# BEATS_3_6.net
KiCad netlist of a schematic drawn in EAGLE
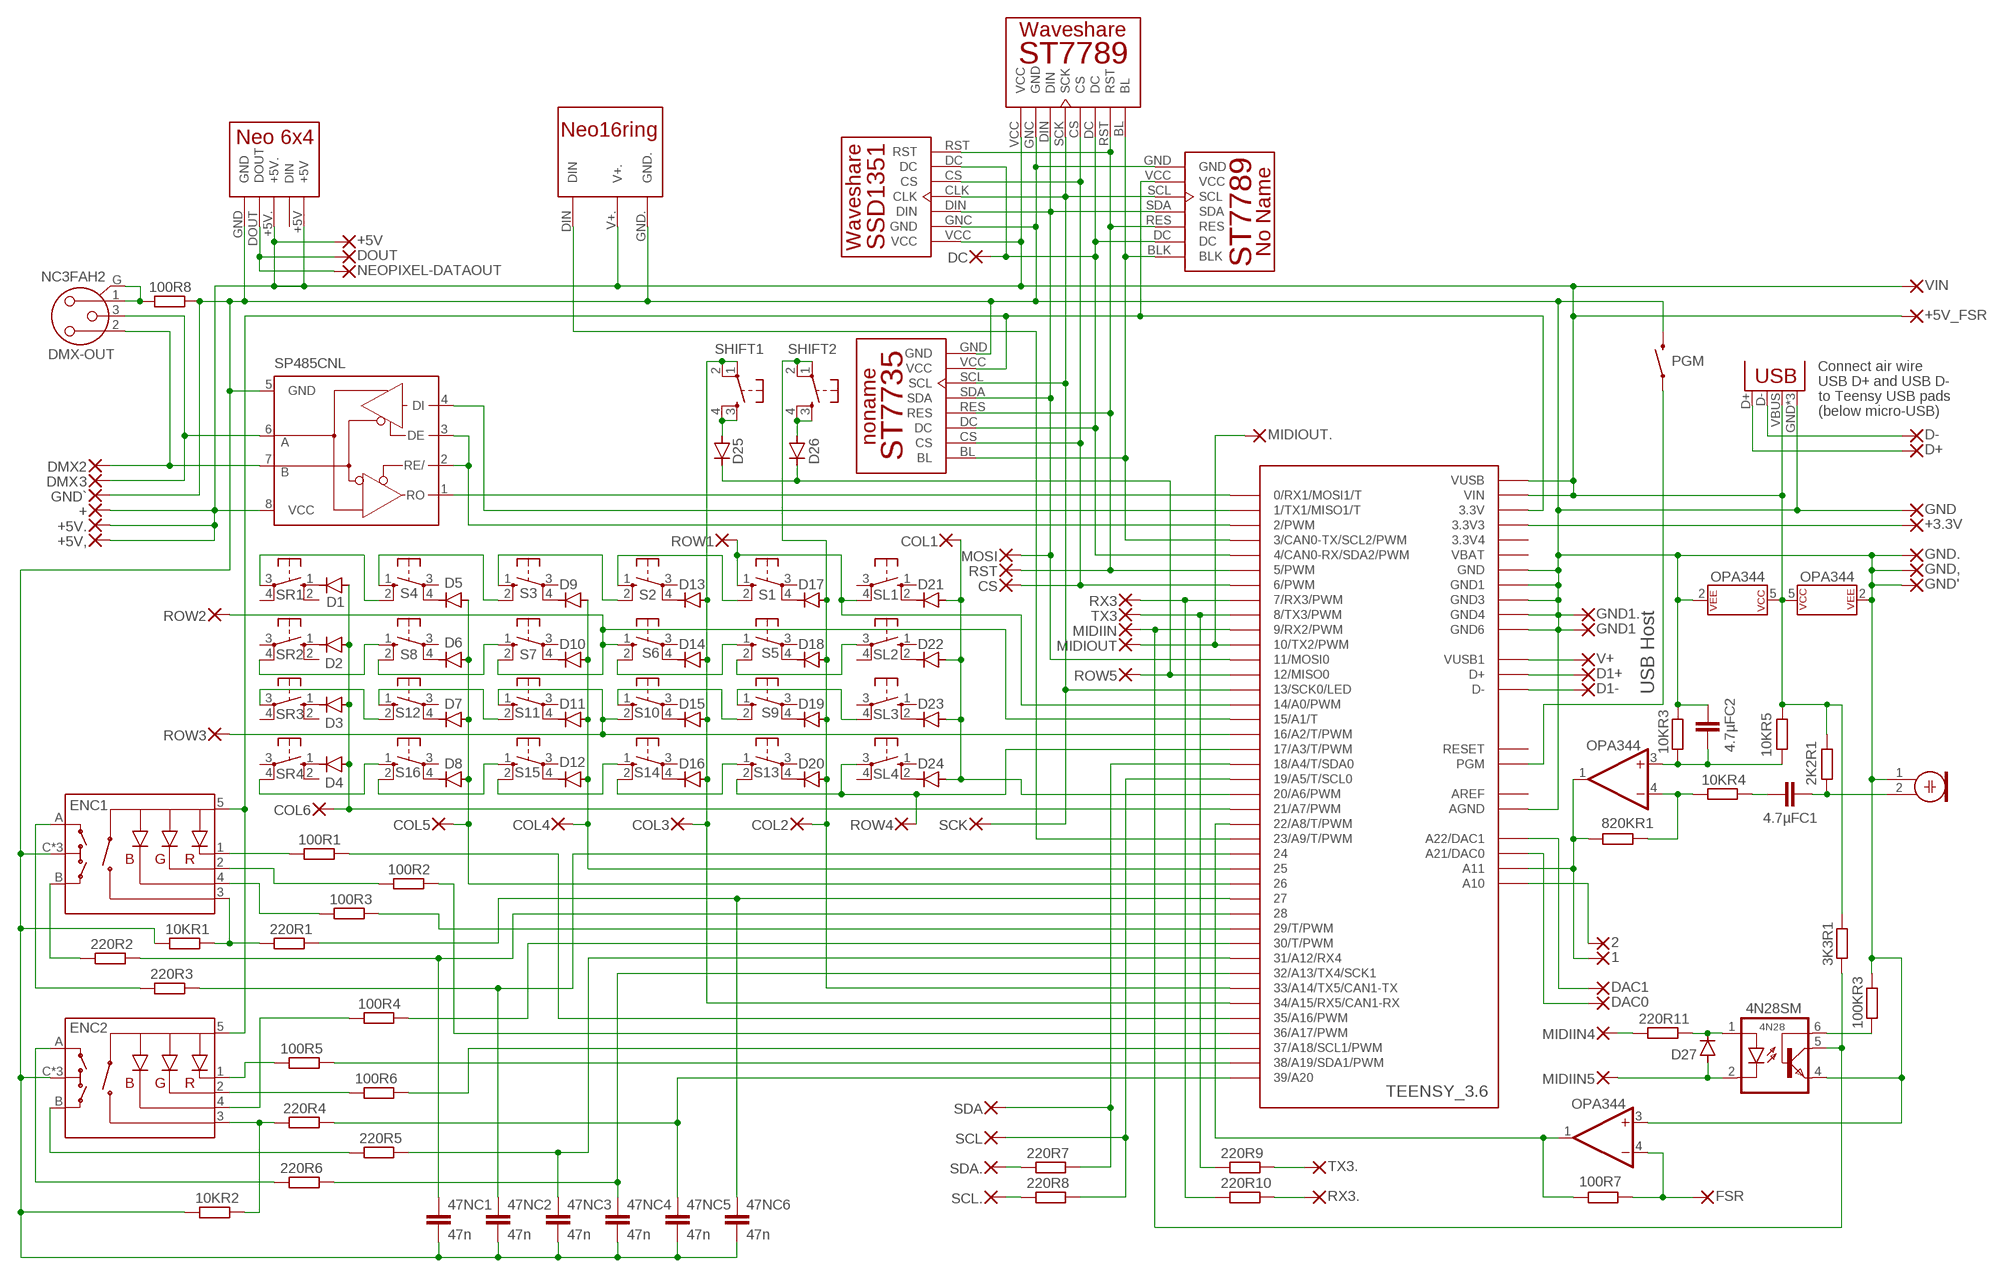
[diagram p0: schematic, sheet 1]

(export (version "E")
  (design (tool "Eeschema 10.0.6"))
  (components
    (comp (ref "+")
      (value "1,6/0,8")
      (footprint "eagle-import:1,6_0,8")
      (libsource (lib "eagle-import") (part "1,6/0,8"))
    )
    (comp (ref "+3.3V")
      (value "+3.3v")
      (footprint "eagle-import:1,6_0,8")
      (libsource (lib "eagle-import") (part "1,6/0,8"))
    )
    (comp (ref "+5V")
      (value "1,6/0,8")
      (footprint "eagle-import:1,6_0,8")
      (libsource (lib "eagle-import") (part "1,6/0,8"))
    )
    (comp (ref "+5V,")
      (value "1,6/0,8")
      (footprint "eagle-import:1,6_0,8")
      (libsource (lib "eagle-import") (part "1,6/0,8"))
    )
    (comp (ref "+5V.")
      (value "1,6/0,8")
      (footprint "eagle-import:1,6_0,8")
      (libsource (lib "eagle-import") (part "1,6/0,8"))
    )
    (comp (ref "+5V_FSR")
      (value "1,6/0,8")
      (footprint "eagle-import:1,6_0,8")
      (libsource (lib "eagle-import") (part "1,6/0,8"))
    )
    (comp (ref "1")
      (value "1,6/0,8")
      (footprint "eagle-import:1,6_0,8")
      (libsource (lib "eagle-import") (part "1,6/0,8"))
    )
    (comp (ref "2")
      (value "1,6/0,8")
      (footprint "eagle-import:1,6_0,8")
      (libsource (lib "eagle-import") (part "1,6/0,8"))
    )
    (comp (ref "2K2R1")
      (value "2K2")
      (footprint "eagle-import:R0603")
      (fields (field (name "SPICEPREFIX") "2K2"))
      (libsource (lib "eagle-import") (part "R-EU_R0603"))
    )
    (comp (ref "3")
      (value "1,6/0,8")
      (footprint "eagle-import:1,6_0,8")
      (libsource (lib "eagle-import") (part "1,6/0,8"))
    )
    (comp (ref "3K3R1")
      (value "3k3")
      (footprint "eagle-import:R0603")
      (fields (field (name "SPICEPREFIX") "3.3K"))
      (libsource (lib "eagle-import") (part "R-EU_R0603"))
    )
    (comp (ref "4.7µFC1")
      (value "4.7µF")
      (footprint "eagle-import:C1210")
      (libsource (lib "eagle-import") (part "rcl_334_C-EUC1210"))
    )
    (comp (ref "4.7µFC2")
      (value "4.7µF")
      (footprint "eagle-import:C1210")
      (libsource (lib "eagle-import") (part "rcl_334_C-EUC1210"))
    )
    (comp (ref "4N28")
      (value "4N28SM")
      (footprint "eagle-import:DIL6-SMD")
      (fields (field (name "MF") "FAIRCHILD SEMICONDUCTOR") (field (name "MPN") "4N28S-M"))
      (libsource (lib "eagle-import") (part "4N?MS28"))
    )
    (comp (ref "10KR1")
      (value "10k")
      (footprint "eagle-import:R0603")
      (fields (field (name "SPICEPREFIX") "2K2"))
      (libsource (lib "eagle-import") (part "R-EU_R0603"))
    )
    (comp (ref "10KR2")
      (value "10k")
      (footprint "eagle-import:R0603")
      (fields (field (name "SPICEPREFIX") "2K2"))
      (libsource (lib "eagle-import") (part "R-EU_R0603"))
    )
    (comp (ref "10KR3")
      (value "10K")
      (footprint "eagle-import:R0603")
      (fields (field (name "SPICEPREFIX") "10K"))
      (libsource (lib "eagle-import") (part "R-EU_R0603"))
    )
    (comp (ref "10KR4")
      (value "10K")
      (footprint "eagle-import:R0603")
      (fields (field (name "SPICEPREFIX") "10K"))
      (libsource (lib "eagle-import") (part "R-EU_R0603"))
    )
    (comp (ref "10KR5")
      (value "10K")
      (footprint "eagle-import:R0603")
      (fields (field (name "SPICEPREFIX") "10K"))
      (libsource (lib "eagle-import") (part "R-EU_R0603"))
    )
    (comp (ref "47NC1")
      (value "47n")
      (footprint "eagle-import:C0603")
      (libsource (lib "eagle-import") (part "C-EUC0603"))
    )
    (comp (ref "47NC2")
      (value "47n")
      (footprint "eagle-import:C0603")
      (libsource (lib "eagle-import") (part "C-EUC0603"))
    )
    (comp (ref "47NC3")
      (value "47n")
      (footprint "eagle-import:C0603")
      (libsource (lib "eagle-import") (part "C-EUC0603"))
    )
    (comp (ref "47NC4")
      (value "47n")
      (footprint "eagle-import:C0603")
      (libsource (lib "eagle-import") (part "C-EUC0603"))
    )
    (comp (ref "47NC5")
      (value "47n")
      (footprint "eagle-import:C0603")
      (libsource (lib "eagle-import") (part "C-EUC0603"))
    )
    (comp (ref "47NC6")
      (value "47n")
      (footprint "eagle-import:C0603")
      (libsource (lib "eagle-import") (part "C-EUC0603"))
    )
    (comp (ref "100KR3")
      (value "100k")
      (footprint "eagle-import:R0603")
      (fields (field (name "SPICEPREFIX") "100K"))
      (libsource (lib "eagle-import") (part "R-EU_R0603"))
    )
    (comp (ref "100R1")
      (value "220R")
      (footprint "eagle-import:R0603")
      (fields (field (name "SPICEPREFIX") "220R"))
      (libsource (lib "eagle-import") (part "R-EU_R0603"))
    )
    (comp (ref "100R2")
      (value "220R")
      (footprint "eagle-import:R0603")
      (fields (field (name "SPICEPREFIX") "220R"))
      (libsource (lib "eagle-import") (part "R-EU_R0603"))
    )
    (comp (ref "100R3")
      (value "220R")
      (footprint "eagle-import:R0603")
      (fields (field (name "SPICEPREFIX") "220R"))
      (libsource (lib "eagle-import") (part "R-EU_R0603"))
    )
    (comp (ref "100R4")
      (value "220R")
      (footprint "eagle-import:R0603")
      (fields (field (name "SPICEPREFIX") "220R"))
      (libsource (lib "eagle-import") (part "R-EU_R0603"))
    )
    (comp (ref "100R5")
      (value "220R")
      (footprint "eagle-import:R0603")
      (fields (field (name "SPICEPREFIX") "220R"))
      (libsource (lib "eagle-import") (part "R-EU_R0603"))
    )
    (comp (ref "100R6")
      (value "220R")
      (footprint "eagle-import:R0603")
      (fields (field (name "SPICEPREFIX") "220R"))
      (libsource (lib "eagle-import") (part "R-EU_R0603"))
    )
    (comp (ref "100R7")
      (value "100R")
      (footprint "eagle-import:R0603")
      (fields (field (name "SPICEPREFIX") "2K2"))
      (libsource (lib "eagle-import") (part "R-EU_R0603"))
    )
    (comp (ref "100R8")
      (value "220R")
      (footprint "eagle-import:R0603")
      (fields (field (name "SPICEPREFIX") "220R"))
      (libsource (lib "eagle-import") (part "R-EU_R0603"))
    )
    (comp (ref "220R1")
      (value "220R")
      (footprint "eagle-import:R0603")
      (fields (field (name "SPICEPREFIX") "220R"))
      (libsource (lib "eagle-import") (part "R-EU_R0603"))
    )
    (comp (ref "220R2")
      (value "220R")
      (footprint "eagle-import:R0603")
      (fields (field (name "SPICEPREFIX") "220R"))
      (libsource (lib "eagle-import") (part "R-EU_R0603"))
    )
    (comp (ref "220R3")
      (value "220R")
      (footprint "eagle-import:R0603")
      (fields (field (name "SPICEPREFIX") "220R"))
      (libsource (lib "eagle-import") (part "R-EU_R0603"))
    )
    (comp (ref "220R4")
      (value "220R")
      (footprint "eagle-import:R0603")
      (fields (field (name "SPICEPREFIX") "220R"))
      (libsource (lib "eagle-import") (part "R-EU_R0603"))
    )
    (comp (ref "220R5")
      (value "220R")
      (footprint "eagle-import:R0603")
      (fields (field (name "SPICEPREFIX") "220R"))
      (libsource (lib "eagle-import") (part "R-EU_R0603"))
    )
    (comp (ref "220R6")
      (value "220R")
      (footprint "eagle-import:R0603")
      (fields (field (name "SPICEPREFIX") "220R"))
      (libsource (lib "eagle-import") (part "R-EU_R0603"))
    )
    (comp (ref "220R7")
      (value "220R")
      (footprint "eagle-import:R0603")
      (fields (field (name "SPICEPREFIX") "220R"))
      (libsource (lib "eagle-import") (part "R-EU_R0603"))
    )
    (comp (ref "220R8")
      (value "220R")
      (footprint "eagle-import:R0603")
      (fields (field (name "SPICEPREFIX") "220R"))
      (libsource (lib "eagle-import") (part "R-EU_R0603"))
    )
    (comp (ref "220R9")
      (value "220R")
      (footprint "eagle-import:R0603")
      (fields (field (name "SPICEPREFIX") "220R"))
      (libsource (lib "eagle-import") (part "R-EU_R0603"))
    )
    (comp (ref "220R10")
      (value "220R")
      (footprint "eagle-import:R0603")
      (fields (field (name "SPICEPREFIX") "220R"))
      (libsource (lib "eagle-import") (part "R-EU_R0603"))
    )
    (comp (ref "220R11")
      (value "220R")
      (footprint "eagle-import:R0603")
      (fields (field (name "SPICEPREFIX") "220R"))
      (libsource (lib "eagle-import") (part "R-EU_R0603"))
    )
    (comp (ref "820KR1")
      (value "820K")
      (footprint "eagle-import:R0603")
      (fields (field (name "SPICEPREFIX") "820K"))
      (libsource (lib "eagle-import") (part "R-EU_R0603"))
    )
    (comp (ref "COL1")
      (value "1,6/0,8")
      (footprint "eagle-import:1,6_0,8")
      (libsource (lib "eagle-import") (part "1,6/0,8"))
    )
    (comp (ref "COL2")
      (value "1,6/0,8")
      (footprint "eagle-import:1,6_0,8")
      (libsource (lib "eagle-import") (part "1,6/0,8"))
    )
    (comp (ref "COL3")
      (value "1,6/0,8")
      (footprint "eagle-import:1,6_0,8")
      (libsource (lib "eagle-import") (part "1,6/0,8"))
    )
    (comp (ref "COL4")
      (value "1,6/0,8")
      (footprint "eagle-import:1,6_0,8")
      (libsource (lib "eagle-import") (part "1,6/0,8"))
    )
    (comp (ref "COL5")
      (value "1,6/0,8")
      (footprint "eagle-import:1,6_0,8")
      (libsource (lib "eagle-import") (part "1,6/0,8"))
    )
    (comp (ref "COL6")
      (value "1,6/0,8")
      (footprint "eagle-import:1,6_0,8")
      (libsource (lib "eagle-import") (part "1,6/0,8"))
    )
    (comp (ref "CS")
      (value "1,6/0,8")
      (footprint "eagle-import:1,6_0,8")
      (libsource (lib "eagle-import") (part "1,6/0,8"))
    )
    (comp (ref "D+")
      (value "1,6/0,8")
      (footprint "eagle-import:1,6_0,8")
      (libsource (lib "eagle-import") (part "1,6/0,8"))
    )
    (comp (ref "D-")
      (value "1,6/0,8")
      (footprint "eagle-import:1,6_0,8")
      (libsource (lib "eagle-import") (part "1,6/0,8"))
    )
    (comp (ref "D1")
      (value "1N4148DO34-5")
      (footprint "eagle-import:DO34-5")
      (libsource (lib "eagle-import") (part "1N4148DO34-5"))
    )
    (comp (ref "D1+")
      (value "1,6/0,8")
      (footprint "eagle-import:1,6_0,8")
      (libsource (lib "eagle-import") (part "1,6/0,8"))
    )
    (comp (ref "D1-")
      (value "1,6/0,8")
      (footprint "eagle-import:1,6_0,8")
      (libsource (lib "eagle-import") (part "1,6/0,8"))
    )
    (comp (ref "D2")
      (value "1N4148DO34-5")
      (footprint "eagle-import:DO34-5")
      (libsource (lib "eagle-import") (part "1N4148DO34-5"))
    )
    (comp (ref "D3")
      (value "1N4148DO34-5")
      (footprint "eagle-import:DO34-5")
      (libsource (lib "eagle-import") (part "1N4148DO34-5"))
    )
    (comp (ref "D4")
      (value "1N4148DO34-5")
      (footprint "eagle-import:DO34-5")
      (libsource (lib "eagle-import") (part "1N4148DO34-5"))
    )
    (comp (ref "D5")
      (value "1N4148DO34-5")
      (footprint "eagle-import:DO34-5")
      (libsource (lib "eagle-import") (part "1N4148DO34-5"))
    )
    (comp (ref "D6")
      (value "1N4148DO34-5")
      (footprint "eagle-import:DO34-5")
      (libsource (lib "eagle-import") (part "1N4148DO34-5"))
    )
    (comp (ref "D7")
      (value "1N4148DO34-5")
      (footprint "eagle-import:DO34-5")
      (libsource (lib "eagle-import") (part "1N4148DO34-5"))
    )
    (comp (ref "D8")
      (value "1N4148DO34-5")
      (footprint "eagle-import:DO34-5")
      (libsource (lib "eagle-import") (part "1N4148DO34-5"))
    )
    (comp (ref "D9")
      (value "1N4148DO34-5")
      (footprint "eagle-import:DO34-5")
      (libsource (lib "eagle-import") (part "1N4148DO34-5"))
    )
    (comp (ref "D10")
      (value "1N4148DO34-5")
      (footprint "eagle-import:DO34-5")
      (libsource (lib "eagle-import") (part "1N4148DO34-5"))
    )
    (comp (ref "D11")
      (value "1N4148DO34-5")
      (footprint "eagle-import:DO34-5")
      (libsource (lib "eagle-import") (part "1N4148DO34-5"))
    )
    (comp (ref "D12")
      (value "1N4148DO34-5")
      (footprint "eagle-import:DO34-5")
      (libsource (lib "eagle-import") (part "1N4148DO34-5"))
    )
    (comp (ref "D13")
      (value "1N4148DO34-5")
      (footprint "eagle-import:DO34-5")
      (libsource (lib "eagle-import") (part "1N4148DO34-5"))
    )
    (comp (ref "D14")
      (value "1N4148DO34-5")
      (footprint "eagle-import:DO34-5")
      (libsource (lib "eagle-import") (part "1N4148DO34-5"))
    )
    (comp (ref "D15")
      (value "1N4148DO34-5")
      (footprint "eagle-import:DO34-5")
      (libsource (lib "eagle-import") (part "1N4148DO34-5"))
    )
    (comp (ref "D16")
      (value "1N4148DO34-5")
      (footprint "eagle-import:DO34-5")
      (libsource (lib "eagle-import") (part "1N4148DO34-5"))
    )
    (comp (ref "D17")
      (value "1N4148DO34-5")
      (footprint "eagle-import:DO34-5")
      (libsource (lib "eagle-import") (part "1N4148DO34-5"))
    )
    (comp (ref "D18")
      (value "1N4148DO34-5")
      (footprint "eagle-import:DO34-5")
      (libsource (lib "eagle-import") (part "1N4148DO34-5"))
    )
    (comp (ref "D19")
      (value "1N4148DO34-5")
      (footprint "eagle-import:DO34-5")
      (libsource (lib "eagle-import") (part "1N4148DO34-5"))
    )
    (comp (ref "D20")
      (value "1N4148DO34-5")
      (footprint "eagle-import:DO34-5")
      (libsource (lib "eagle-import") (part "1N4148DO34-5"))
    )
    (comp (ref "D21")
      (value "1N4148DO34-5")
      (footprint "eagle-import:DO34-5")
      (libsource (lib "eagle-import") (part "1N4148DO34-5"))
    )
    (comp (ref "D22")
      (value "1N4148DO34-5")
      (footprint "eagle-import:DO34-5")
      (libsource (lib "eagle-import") (part "1N4148DO34-5"))
    )
    (comp (ref "D23")
      (value "1N4148DO34-5")
      (footprint "eagle-import:DO34-5")
      (libsource (lib "eagle-import") (part "1N4148DO34-5"))
    )
    (comp (ref "D24")
      (value "1N4148DO34-5")
      (footprint "eagle-import:DO34-5")
      (libsource (lib "eagle-import") (part "1N4148DO34-5"))
    )
    (comp (ref "D25")
      (value "1N4148DO34-5")
      (footprint "eagle-import:DO34-5")
      (libsource (lib "eagle-import") (part "1N4148DO34-5"))
    )
    (comp (ref "D26")
      (value "1N4148DO34-5")
      (footprint "eagle-import:DO34-5")
      (libsource (lib "eagle-import") (part "1N4148DO34-5"))
    )
    (comp (ref "D27")
      (value "1N4148DO34-5")
      (footprint "eagle-import:DO34-5")
      (libsource (lib "eagle-import") (part "1N4148DO34-5"))
    )
    (comp (ref "DAC0")
      (value "1,6/0,8")
      (footprint "eagle-import:1,6_0,8")
      (libsource (lib "eagle-import") (part "1,6/0,8"))
    )
    (comp (ref "DAC1")
      (value "1,6/0,8")
      (footprint "eagle-import:1,6_0,8")
      (libsource (lib "eagle-import") (part "1,6/0,8"))
    )
    (comp (ref "DC")
      (value "1,6/0,8")
      (footprint "eagle-import:1,6_0,8")
      (libsource (lib "eagle-import") (part "1,6/0,8"))
    )
    (comp (ref "DMX-OUT")
      (value "NC3FAH2")
      (footprint "eagle-import:NC3FAH2")
      (libsource (lib "eagle-import") (part "NC3FAH2"))
    )
    (comp (ref "DMX2")
      (value "1,6/0,8")
      (footprint "eagle-import:1,6_0,8")
      (libsource (lib "eagle-import") (part "1,6/0,8"))
    )
    (comp (ref "DOUT")
      (value "1,6/0,8")
      (footprint "eagle-import:1,6_0,8")
      (libsource (lib "eagle-import") (part "1,6/0,8"))
    )
    (comp (ref "ENC1")
      (value "ENCODER-RGB-SWITCHENCODER_LED_3_LONG")
      (footprint "eagle-import:ENCODER_LED_3_LONG")
      (libsource (lib "eagle-import") (part "ENCODER-RGB-SWITCHENCODER_LED_3_LONG"))
    )
    (comp (ref "ENC2")
      (value "ENCODER-RGB-SWITCHENCODER_LED_3_LONG")
      (footprint "eagle-import:ENCODER_LED_3_LONG")
      (libsource (lib "eagle-import") (part "ENCODER-RGB-SWITCHENCODER_LED_3_LONG"))
    )
    (comp (ref "FSR")
      (value "1,6/0,8")
      (footprint "eagle-import:1,6_0,8")
      (libsource (lib "eagle-import") (part "1,6/0,8"))
    )
    (comp (ref "GND")
      (value "1,6/0,8")
      (footprint "eagle-import:1,6_0,8")
      (libsource (lib "eagle-import") (part "1,6/0,8"))
    )
    (comp (ref "GND'")
      (value "1,6/0,8")
      (footprint "eagle-import:1,6_0,8")
      (libsource (lib "eagle-import") (part "1,6/0,8"))
    )
    (comp (ref "GND,")
      (value "1,6/0,8")
      (footprint "eagle-import:1,6_0,8")
      (libsource (lib "eagle-import") (part "1,6/0,8"))
    )
    (comp (ref "GND.")
      (value "1,6/0,8")
      (footprint "eagle-import:1,6_0,8")
      (libsource (lib "eagle-import") (part "1,6/0,8"))
    )
    (comp (ref "GND1")
      (value "1,6/0,8")
      (footprint "eagle-import:1,6_0,8")
      (libsource (lib "eagle-import") (part "1,6/0,8"))
    )
    (comp (ref "GND1.")
      (value "1,6/0,8")
      (footprint "eagle-import:1,6_0,8")
      (libsource (lib "eagle-import") (part "1,6/0,8"))
    )
    (comp (ref "GND`")
      (value "1,6/0,8")
      (footprint "eagle-import:1,6_0,8")
      (libsource (lib "eagle-import") (part "1,6/0,8"))
    )
    (comp (ref "MIC")
      (value "ELECTRET_MICROPHON-F6035AP")
      (footprint "eagle-import:F6035AP")
      (libsource (lib "eagle-import") (part "ELECTRET_MICROPHON-F6035AP"))
    )
    (comp (ref "MIDIIN")
      (value "1,6/0,8")
      (footprint "eagle-import:1,6_0,8")
      (libsource (lib "eagle-import") (part "1,6/0,8"))
    )
    (comp (ref "MIDIIN4")
      (value "1,6/0,8")
      (footprint "eagle-import:1,6_0,8")
      (libsource (lib "eagle-import") (part "1,6/0,8"))
    )
    (comp (ref "MIDIIN5")
      (value "1,6/0,8")
      (footprint "eagle-import:1,6_0,8")
      (libsource (lib "eagle-import") (part "1,6/0,8"))
    )
    (comp (ref "MIDIOUT")
      (value "1,6/0,8")
      (footprint "eagle-import:1,6_0,8")
      (libsource (lib "eagle-import") (part "1,6/0,8"))
    )
    (comp (ref "MIDIOUT.")
      (value "1,6/0,8")
      (footprint "eagle-import:1,6_0,8")
      (libsource (lib "eagle-import") (part "1,6/0,8"))
    )
    (comp (ref "MOSI")
      (value "1,6/0,8")
      (footprint "eagle-import:1,6_0,8")
      (libsource (lib "eagle-import") (part "1,6/0,8"))
    )
    (comp (ref "NEOPIXEL-DATAOUT")
      (value "1,6/0,8")
      (footprint "eagle-import:1,6_0,8")
      (libsource (lib "eagle-import") (part "1,6/0,8"))
    )
    (comp (ref "OPA348,")
      (value "OPA344")
      (footprint "eagle-import:SOT23-5")
      (libsource (lib "eagle-import") (part "OPA344"))
    )
    (comp (ref "OPA348.")
      (value "OPA344")
      (footprint "eagle-import:SOT23-5")
      (libsource (lib "eagle-import") (part "OPA344"))
    )
    (comp (ref "PGM")
      (value "MOMENTARY-SWITCH-SPST-SMD-4.6X2.8MM")
      (footprint "eagle-import:TACTILE_SWITCH_SMD_4.6X2.8MM")
      (libsource (lib "eagle-import") (part "MOMENTARY-SWITCH-SPST-SMD-4.6X2.8MM"))
    )
    (comp (ref "ROW1")
      (value "1,6/0,8")
      (footprint "eagle-import:1,6_0,8")
      (libsource (lib "eagle-import") (part "1,6/0,8"))
    )
    (comp (ref "ROW2")
      (value "1,6/0,8")
      (footprint "eagle-import:1,6_0,8")
      (libsource (lib "eagle-import") (part "1,6/0,8"))
    )
    (comp (ref "ROW3")
      (value "1,6/0,8")
      (footprint "eagle-import:1,6_0,8")
      (libsource (lib "eagle-import") (part "1,6/0,8"))
    )
    (comp (ref "ROW4")
      (value "1,6/0,8")
      (footprint "eagle-import:1,6_0,8")
      (libsource (lib "eagle-import") (part "1,6/0,8"))
    )
    (comp (ref "ROW5")
      (value "1,6/0,8")
      (footprint "eagle-import:1,6_0,8")
      (libsource (lib "eagle-import") (part "1,6/0,8"))
    )
    (comp (ref "RST")
      (value "1,6/0,8")
      (footprint "eagle-import:1,6_0,8")
      (libsource (lib "eagle-import") (part "1,6/0,8"))
    )
    (comp (ref "RX3")
      (value "1,6/0,8")
      (footprint "eagle-import:1,6_0,8")
      (libsource (lib "eagle-import") (part "1,6/0,8"))
    )
    (comp (ref "RX3.")
      (value "1,6/0,8")
      (footprint "eagle-import:1,6_0,8")
      (libsource (lib "eagle-import") (part "1,6/0,8"))
    )
    (comp (ref "S1")
      (value "10-XXLONG")
      (footprint "eagle-import:B3F-10XX")
      (fields (field (name "MPN") "B3F-1000"))
      (libsource (lib "eagle-import") (part "10-XXLONG"))
    )
    (comp (ref "S2")
      (value "10-XXLONG")
      (footprint "eagle-import:B3F-10XX")
      (fields (field (name "MPN") "B3F-1000"))
      (libsource (lib "eagle-import") (part "10-XXLONG"))
    )
    (comp (ref "S3")
      (value "10-XXLONG")
      (footprint "eagle-import:B3F-10XX")
      (fields (field (name "MPN") "B3F-1000"))
      (libsource (lib "eagle-import") (part "10-XXLONG"))
    )
    (comp (ref "S4")
      (value "10-XXLONG")
      (footprint "eagle-import:B3F-10XX")
      (fields (field (name "MPN") "B3F-1000"))
      (libsource (lib "eagle-import") (part "10-XXLONG"))
    )
    (comp (ref "S5")
      (value "10-XXLONG")
      (footprint "eagle-import:B3F-10XX")
      (fields (field (name "MPN") "B3F-1000"))
      (libsource (lib "eagle-import") (part "10-XXLONG"))
    )
    (comp (ref "S6")
      (value "10-XXLONG")
      (footprint "eagle-import:B3F-10XX")
      (fields (field (name "MPN") "B3F-1000"))
      (libsource (lib "eagle-import") (part "10-XXLONG"))
    )
    (comp (ref "S7")
      (value "10-XXLONG")
      (footprint "eagle-import:B3F-10XX")
      (fields (field (name "MPN") "B3F-1000"))
      (libsource (lib "eagle-import") (part "10-XXLONG"))
    )
    (comp (ref "S8")
      (value "10-XXLONG")
      (footprint "eagle-import:B3F-10XX")
      (fields (field (name "MPN") "B3F-1000"))
      (libsource (lib "eagle-import") (part "10-XXLONG"))
    )
    (comp (ref "S9")
      (value "10-XXLONG")
      (footprint "eagle-import:B3F-10XX")
      (fields (field (name "MPN") "B3F-1000"))
      (libsource (lib "eagle-import") (part "10-XXLONG"))
    )
    (comp (ref "S10")
      (value "10-XXLONG")
      (footprint "eagle-import:B3F-10XX")
      (fields (field (name "MPN") "B3F-1000"))
      (libsource (lib "eagle-import") (part "10-XXLONG"))
    )
    (comp (ref "S11")
      (value "10-XXLONG")
      (footprint "eagle-import:B3F-10XX")
      (fields (field (name "MPN") "B3F-1000"))
      (libsource (lib "eagle-import") (part "10-XXLONG"))
    )
    (comp (ref "S12")
      (value "10-XXLONG")
      (footprint "eagle-import:B3F-10XX")
      (fields (field (name "MPN") "B3F-1000"))
      (libsource (lib "eagle-import") (part "10-XXLONG"))
    )
    (comp (ref "S13")
      (value "10-XXLONG")
      (footprint "eagle-import:B3F-10XX")
      (fields (field (name "MPN") "B3F-1000"))
      (libsource (lib "eagle-import") (part "10-XXLONG"))
    )
    (comp (ref "S14")
      (value "10-XXLONG")
      (footprint "eagle-import:B3F-10XX")
      (fields (field (name "MPN") "B3F-1000"))
      (libsource (lib "eagle-import") (part "10-XXLONG"))
    )
    (comp (ref "S15")
      (value "10-XXLONG")
      (footprint "eagle-import:B3F-10XX")
      (fields (field (name "MPN") "B3F-1000"))
      (libsource (lib "eagle-import") (part "10-XXLONG"))
    )
    (comp (ref "S16")
      (value "10-XXLONG")
      (footprint "eagle-import:B3F-10XX")
      (fields (field (name "MPN") "B3F-1000"))
      (libsource (lib "eagle-import") (part "10-XXLONG"))
    )
    (comp (ref "SCK")
      (value "1,6/0,8")
      (footprint "eagle-import:1,6_0,8")
      (libsource (lib "eagle-import") (part "1,6/0,8"))
    )
    (comp (ref "SCL")
      (value "1,6/0,8")
      (footprint "eagle-import:1,6_0,8")
      (libsource (lib "eagle-import") (part "1,6/0,8"))
    )
    (comp (ref "SCL.")
      (value "1,6/0,8")
      (footprint "eagle-import:1,6_0,8")
      (libsource (lib "eagle-import") (part "1,6/0,8"))
    )
    (comp (ref "SDA")
      (value "1,6/0,8")
      (footprint "eagle-import:1,6_0,8")
      (libsource (lib "eagle-import") (part "1,6/0,8"))
    )
    (comp (ref "SDA.")
      (value "1,6/0,8")
      (footprint "eagle-import:1,6_0,8")
      (libsource (lib "eagle-import") (part "1,6/0,8"))
    )
    (comp (ref "SHIFT1")
      (value "MOMENTARY-SWITCH-SPST-2-SMD-5.2MM")
      (footprint "eagle-import:TACTILE_SWITCH_SMD_5.2MM")
      (libsource (lib "eagle-import") (part "MOMENTARY-SWITCH-SPST-2-SMD-5.2MM"))
    )
    (comp (ref "SHIFT2")
      (value "MOMENTARY-SWITCH-SPST-2-SMD-5.2MM")
      (footprint "eagle-import:TACTILE_SWITCH_SMD_5.2MM")
      (libsource (lib "eagle-import") (part "MOMENTARY-SWITCH-SPST-2-SMD-5.2MM"))
    )
    (comp (ref "SL1")
      (value "10-XXIN")
      (footprint "eagle-import:B3F-10XX1")
      (libsource (lib "eagle-import") (part "10-XXIN"))
    )
    (comp (ref "SL2")
      (value "10-XXIN")
      (footprint "eagle-import:B3F-10XX1")
      (libsource (lib "eagle-import") (part "10-XXIN"))
    )
    (comp (ref "SL3")
      (value "10-XXIN")
      (footprint "eagle-import:B3F-10XX1")
      (libsource (lib "eagle-import") (part "10-XXIN"))
    )
    (comp (ref "SL4")
      (value "10-XXIN")
      (footprint "eagle-import:B3F-10XX1")
      (libsource (lib "eagle-import") (part "10-XXIN"))
    )
    (comp (ref "SP485CNL")
      (value "MAX3468CSA")
      (footprint "eagle-import:SO08")
      (fields (field (name "MPN") "MAX3468CSA+"))
      (libsource (lib "eagle-import") (part "MAX34SA68C"))
    )
    (comp (ref "SR1")
      (value "10-XXIN")
      (footprint "eagle-import:B3F-10XX1")
      (libsource (lib "eagle-import") (part "10-XXIN"))
    )
    (comp (ref "SR2")
      (value "10-XXIN")
      (footprint "eagle-import:B3F-10XX1")
      (libsource (lib "eagle-import") (part "10-XXIN"))
    )
    (comp (ref "SR3")
      (value "10-XXIN")
      (footprint "eagle-import:B3F-10XX1")
      (libsource (lib "eagle-import") (part "10-XXIN"))
    )
    (comp (ref "SR4")
      (value "10-XXIN")
      (footprint "eagle-import:B3F-10XX1")
      (libsource (lib "eagle-import") (part "10-XXIN"))
    )
    (comp (ref "TEENSY_3.6")
      (value "TEENSY_3.6_ALL_PINS")
      (footprint "eagle-import:TEENSY_3.6_ALL_PINS")
      (libsource (lib "eagle-import") (part "TEENSY_3.6_ALL_PINS"))
    )
    (comp (ref "TX3")
      (value "1,6/0,8")
      (footprint "eagle-import:1,6_0,8")
      (libsource (lib "eagle-import") (part "1,6/0,8"))
    )
    (comp (ref "TX3.")
      (value "1,6/0,8")
      (footprint "eagle-import:1,6_0,8")
      (libsource (lib "eagle-import") (part "1,6/0,8"))
    )
    (comp (ref "U$1")
      (value "WS_1.3\"240X240_3.3V")
      (footprint "eagle-import:WS_1.3_240X240_3.3V")
      (libsource (lib "eagle-import") (part "WS_1.3{dblquote}240X240_3.3V"))
    )
    (comp (ref "U$2")
      (value "WS_1.5\"128X128_OLEDOLED")
      (footprint "eagle-import:WS_1.5_128X128_OLED")
      (libsource (lib "eagle-import") (part "WS_1.5{dblquote}128X128_OLEDOLED"))
    )
    (comp (ref "U$3")
      (value "WS_1.3\"240X240ROUND")
      (footprint "eagle-import:WS_1.3_240X240_ROUND")
      (libsource (lib "eagle-import") (part "WS_1.3{dblquote}240X240ROUND"))
    )
    (comp (ref "U$4")
      (value "NEO16RING")
      (footprint "eagle-import:NEO16RING")
      (libsource (lib "eagle-import") (part "NEO16RING"))
    )
    (comp (ref "U$5")
      (value "WS_1.44\"128X128WS_1.44\"128X128")
      (footprint "eagle-import:WS_1.44_128X128")
      (libsource (lib "eagle-import") (part "WS_1.44{dblquote}128X128WS_1.44{dblquote}128X128"))
    )
    (comp (ref "U$7")
      (value "NEOPIXEL_6X4")
      (footprint "eagle-import:NEOPIXEL_6X4")
      (libsource (lib "eagle-import") (part "NEOPIXEL_6X4"))
    )
    (comp (ref "USB-B")
      (value "USB-B-H")
      (footprint "eagle-import:USB-B-H")
      (libsource (lib "eagle-import") (part "USB-B-H"))
    )
    (comp (ref "V+")
      (value "1,6/0,8")
      (footprint "eagle-import:1,6_0,8")
      (libsource (lib "eagle-import") (part "1,6/0,8"))
    )
    (comp (ref "VIN")
      (value "+3.3v")
      (footprint "eagle-import:1,6_0,8")
      (libsource (lib "eagle-import") (part "1,6/0,8"))
    )
  )
  (nets
    (net (code "1") (name "/3.3V4") (class "Default")
      (node (ref "TEENSY_3.6") (pin "3.3V4") (pinfunction "3.3V4_3.3V4") (pintype "power_in"))
    )
    (net (code "2") (name "/AREF") (class "Default")
      (node (ref "TEENSY_3.6") (pin "AREF") (pinfunction "AREF_AREF") (pintype "power_in"))
    )
    (net (code "3") (name "/VBAT") (class "Default")
      (node (ref "TEENSY_3.6") (pin "VBAT") (pinfunction "VBAT_VBAT") (pintype "power_in"))
    )
    (net (code "4") (name "Net-(+-P)") (class "Default")
      (node (ref "+") (pin "1") (pinfunction "P_1") (pintype "passive"))
      (node (ref "+5V") (pin "1") (pinfunction "P_1") (pintype "passive"))
      (node (ref "+5V,") (pin "1") (pinfunction "P_1") (pintype "passive"))
      (node (ref "+5V.") (pin "1") (pinfunction "P_1") (pintype "passive"))
      (node (ref "+5V_FSR") (pin "1") (pinfunction "P_1") (pintype "passive"))
      (node (ref "10KR5") (pin "2") (pinfunction "2_2") (pintype "passive"))
      (node (ref "2K2R1") (pin "2") (pinfunction "2_2") (pintype "passive"))
      (node (ref "3K3R1") (pin "1") (pinfunction "1_1") (pintype "passive"))
      (node (ref "OPA348,") (pin "5") (pinfunction "P$V+_5") (pintype "bidirectional"))
      (node (ref "OPA348.") (pin "5") (pinfunction "P$V+_5") (pintype "bidirectional"))
      (node (ref "SP485CNL") (pin "8") (pinfunction "VCC_8") (pintype "power_in"))
      (node (ref "TEENSY_3.6") (pin "VIN") (pinfunction "VIN_VIN") (pintype "power_in"))
      (node (ref "TEENSY_3.6") (pin "VUSB") (pinfunction "VUSB_VUSB") (pintype "power_in"))
      (node (ref "U$2") (pin "VCC") (pinfunction "VCC_VCC") (pintype "power_in"))
      (node (ref "U$3") (pin "VCC") (pinfunction "VCC_VCC") (pintype "power_in"))
      (node (ref "U$4") (pin "V+.") (pinfunction "V+._V+.") (pintype "power_in"))
      (node (ref "U$7") (pin "+5V") (pinfunction "+5V_+5V") (pintype "bidirectional"))
      (node (ref "U$7") (pin "+5V.") (pinfunction "+5V._+5V.") (pintype "bidirectional"))
      (node (ref "USB-B") (pin "VBUS") (pinfunction "VBUS_VBUS") (pintype "bidirectional"))
      (node (ref "VIN") (pin "1") (pinfunction "P_1") (pintype "passive"))
    )
    (net (code "5") (name "Net-(+3.3V-P)") (class "Default")
      (node (ref "+3.3V") (pin "1") (pinfunction "P_1") (pintype "passive"))
      (node (ref "TEENSY_3.6") (pin "3.3V3") (pinfunction "3.3V3_3.3V3") (pintype "power_in"))
    )
    (net (code "6") (name "Net-(1-P)") (class "Default")
      (node (ref "1") (pin "1") (pinfunction "P_1") (pintype "passive"))
      (node (ref "820KR1") (pin "1") (pinfunction "1_1") (pintype "passive"))
      (node (ref "OPA348.") (pin "1") (pinfunction "OUT_1") (pintype "output"))
      (node (ref "TEENSY_3.6") (pin "A11") (pinfunction "A11_A11") (pintype "bidirectional"))
    )
    (net (code "7") (name "Net-(2-P)") (class "Default")
      (node (ref "2") (pin "1") (pinfunction "P_1") (pintype "passive"))
      (node (ref "TEENSY_3.6") (pin "A10") (pinfunction "A10_A10") (pintype "bidirectional"))
    )
    (net (code "8") (name "Net-(2K2R1-Pad1)") (class "Default")
      (node (ref "2K2R1") (pin "1") (pinfunction "1_1") (pintype "passive"))
      (node (ref "4.7µFC1") (pin "2") (pinfunction "2_2") (pintype "passive"))
      (node (ref "MIC") (pin "2") (pinfunction "2_2") (pintype "passive"))
    )
    (net (code "9") (name "Net-(3-P)") (class "Default")
      (node (ref "3") (pin "1") (pinfunction "P_1") (pintype "passive"))
      (node (ref "DMX-OUT") (pin "3") (pinfunction "3_3") (pintype "passive"))
      (node (ref "SP485CNL") (pin "6") (pinfunction "A_6") (pintype "passive"))
    )
    (net (code "10") (name "Net-(4N28-A)") (class "Default")
      (node (ref "220R11") (pin "2") (pinfunction "2_2") (pintype "passive"))
      (node (ref "4N28") (pin "1") (pinfunction "A_1") (pintype "passive"))
      (node (ref "D27") (pin "C") (pinfunction "C_C") (pintype "passive"))
    )
    (net (code "11") (name "Net-(4N28-BAS)") (class "Default")
      (node (ref "100KR3") (pin "1") (pinfunction "1_1") (pintype "passive"))
      (node (ref "4N28") (pin "6") (pinfunction "BAS_6") (pintype "passive"))
    )
    (net (code "12") (name "Net-(4N28-C)") (class "Default")
      (node (ref "4N28") (pin "2") (pinfunction "C_2") (pintype "passive"))
      (node (ref "D27") (pin "A") (pinfunction "A_A") (pintype "passive"))
      (node (ref "MIDIIN5") (pin "1") (pinfunction "P_1") (pintype "passive"))
    )
    (net (code "13") (name "Net-(4N28-COL)") (class "Default")
      (node (ref "3K3R1") (pin "2") (pinfunction "2_2") (pintype "passive"))
      (node (ref "4N28") (pin "5") (pinfunction "COL_5") (pintype "passive"))
      (node (ref "MIDIIN") (pin "1") (pinfunction "P_1") (pintype "passive"))
      (node (ref "TEENSY_3.6") (pin "9") (pinfunction "9/RX2/PWM_9") (pintype "bidirectional"))
    )
    (net (code "14") (name "Net-(4N28-EMI)") (class "Default")
      (node (ref "100KR3") (pin "2") (pinfunction "2_2") (pintype "passive"))
      (node (ref "100R8") (pin "2") (pinfunction "2_2") (pintype "passive"))
      (node (ref "10KR1") (pin "1") (pinfunction "1_1") (pintype "passive"))
      (node (ref "10KR2") (pin "1") (pinfunction "1_1") (pintype "passive"))
      (node (ref "10KR3") (pin "2") (pinfunction "2_2") (pintype "passive"))
      (node (ref "4.7µFC2") (pin "1") (pinfunction "1_1") (pintype "passive"))
      (node (ref "47NC1") (pin "2") (pinfunction "2_2") (pintype "passive"))
      (node (ref "47NC2") (pin "2") (pinfunction "2_2") (pintype "passive"))
      (node (ref "47NC3") (pin "2") (pinfunction "2_2") (pintype "passive"))
      (node (ref "47NC4") (pin "2") (pinfunction "2_2") (pintype "passive"))
      (node (ref "47NC5") (pin "2") (pinfunction "2_2") (pintype "passive"))
      (node (ref "47NC6") (pin "2") (pinfunction "2_2") (pintype "passive"))
      (node (ref "4N28") (pin "4") (pinfunction "EMI_4") (pintype "passive"))
      (node (ref "ENC1") (pin "C") (pinfunction "C_C") (pintype "bidirectional"))
      (node (ref "ENC1") (pin "M1") (pinfunction "C_M1") (pintype "bidirectional"))
      (node (ref "ENC1") (pin "M2") (pinfunction "C_M2") (pintype "bidirectional"))
      (node (ref "ENC2") (pin "C") (pinfunction "C_C") (pintype "bidirectional"))
      (node (ref "ENC2") (pin "M1") (pinfunction "C_M1") (pintype "bidirectional"))
      (node (ref "ENC2") (pin "M2") (pinfunction "C_M2") (pintype "bidirectional"))
      (node (ref "GND") (pin "1") (pinfunction "P_1") (pintype "passive"))
      (node (ref "GND'") (pin "1") (pinfunction "P_1") (pintype "passive"))
      (node (ref "GND,") (pin "1") (pinfunction "P_1") (pintype "passive"))
      (node (ref "GND.") (pin "1") (pinfunction "P_1") (pintype "passive"))
      (node (ref "GND1") (pin "1") (pinfunction "P_1") (pintype "passive"))
      (node (ref "GND1.") (pin "1") (pinfunction "P_1") (pintype "passive"))
      (node (ref "GND`") (pin "1") (pinfunction "P_1") (pintype "passive"))
      (node (ref "MIC") (pin "1") (pinfunction "1_1") (pintype "passive"))
      (node (ref "OPA348,") (pin "2") (pinfunction "P$V-_2") (pintype "bidirectional"))
      (node (ref "OPA348,") (pin "3") (pinfunction "+IN_3") (pintype "input"))
      (node (ref "OPA348.") (pin "2") (pinfunction "P$V-_2") (pintype "bidirectional"))
      (node (ref "PGM") (pin "3") (pinfunction "2_3") (pintype "passive"))
      (node (ref "PGM") (pin "4") (pinfunction "2_4") (pintype "passive"))
      (node (ref "SP485CNL") (pin "5") (pinfunction "GND_5") (pintype "power_in"))
      (node (ref "TEENSY_3.6") (pin "AGND") (pinfunction "AGND_AGND") (pintype "power_in"))
      (node (ref "TEENSY_3.6") (pin "GND") (pinfunction "GND_GND") (pintype "power_in"))
      (node (ref "TEENSY_3.6") (pin "GND1") (pinfunction "GND1_GND1") (pintype "power_in"))
      (node (ref "TEENSY_3.6") (pin "GND3") (pinfunction "GND3_GND3") (pintype "power_in"))
      (node (ref "TEENSY_3.6") (pin "GND4") (pinfunction "GND4_GND4") (pintype "power_in"))
      (node (ref "TEENSY_3.6") (pin "GND6") (pinfunction "GND6_GND6") (pintype "power_in"))
      (node (ref "U$1") (pin "GND") (pinfunction "GND_GND") (pintype "power_in"))
      (node (ref "U$2") (pin "GNC") (pinfunction "GND_GNC") (pintype "power_in"))
      (node (ref "U$3") (pin "GNC") (pinfunction "GND_GNC") (pintype "power_in"))
      (node (ref "U$4") (pin "GND.") (pinfunction "GND._GND.") (pintype "power_in"))
      (node (ref "U$5") (pin "GND") (pinfunction "GND_GND") (pintype "power_in"))
      (node (ref "U$7") (pin "GND") (pinfunction "GND_GND") (pintype "bidirectional"))
      (node (ref "USB-B") (pin "GND") (pinfunction "GND_GND") (pintype "bidirectional"))
      (node (ref "USB-B") (pin "P$1") (pinfunction "GND_P$1") (pintype "bidirectional"))
      (node (ref "USB-B") (pin "P$2") (pinfunction "GND_P$2") (pintype "bidirectional"))
    )
    (net (code "15") (name "Net-(10KR4-Pad2)") (class "Default")
      (node (ref "10KR4") (pin "2") (pinfunction "2_2") (pintype "passive"))
      (node (ref "4.7µFC1") (pin "1") (pinfunction "1_1") (pintype "passive"))
    )
    (net (code "16") (name "Net-(220R1-Pad2)") (class "Default")
      (node (ref "220R1") (pin "2") (pinfunction "2_2") (pintype "passive"))
      (node (ref "47NC6") (pin "1") (pinfunction "1_1") (pintype "passive"))
      (node (ref "TEENSY_3.6") (pin "27") (pinfunction "27_27") (pintype "bidirectional"))
    )
    (net (code "17") (name "Net-(220R2-Pad1)") (class "Default")
      (node (ref "220R2") (pin "1") (pinfunction "1_1") (pintype "passive"))
      (node (ref "ENC1") (pin "B") (pinfunction "B_B") (pintype "bidirectional"))
    )
    (net (code "18") (name "Net-(220R2-Pad2)") (class "Default")
      (node (ref "220R2") (pin "2") (pinfunction "2_2") (pintype "passive"))
      (node (ref "47NC1") (pin "1") (pinfunction "1_1") (pintype "passive"))
      (node (ref "TEENSY_3.6") (pin "28") (pinfunction "28_28") (pintype "bidirectional"))
    )
    (net (code "19") (name "Net-(220R3-Pad1)") (class "Default")
      (node (ref "220R3") (pin "1") (pinfunction "1_1") (pintype "passive"))
      (node (ref "ENC1") (pin "A") (pinfunction "A_A") (pintype "bidirectional"))
    )
    (net (code "20") (name "Net-(220R3-Pad2)") (class "Default")
      (node (ref "220R3") (pin "2") (pinfunction "2_2") (pintype "passive"))
      (node (ref "47NC2") (pin "1") (pinfunction "1_1") (pintype "passive"))
      (node (ref "TEENSY_3.6") (pin "24") (pinfunction "24_24") (pintype "bidirectional"))
    )
    (net (code "21") (name "Net-(220R4-Pad2)") (class "Default")
      (node (ref "220R4") (pin "2") (pinfunction "2_2") (pintype "passive"))
      (node (ref "47NC5") (pin "1") (pinfunction "1_1") (pintype "passive"))
      (node (ref "TEENSY_3.6") (pin "39/A20") (pinfunction "39/A20_39/A20") (pintype "bidirectional"))
    )
    (net (code "22") (name "Net-(220R5-Pad1)") (class "Default")
      (node (ref "220R5") (pin "1") (pinfunction "1_1") (pintype "passive"))
      (node (ref "ENC2") (pin "B") (pinfunction "B_B") (pintype "bidirectional"))
    )
    (net (code "23") (name "Net-(220R6-Pad1)") (class "Default")
      (node (ref "220R6") (pin "1") (pinfunction "1_1") (pintype "passive"))
      (node (ref "ENC2") (pin "A") (pinfunction "A_A") (pintype "bidirectional"))
    )
    (net (code "24") (name "Net-(COL1-P)") (class "Default")
      (node (ref "COL1") (pin "1") (pinfunction "P_1") (pintype "passive"))
      (node (ref "D21") (pin "A") (pinfunction "A_A") (pintype "passive"))
      (node (ref "D22") (pin "A") (pinfunction "A_A") (pintype "passive"))
      (node (ref "D23") (pin "A") (pinfunction "A_A") (pintype "passive"))
      (node (ref "D24") (pin "A") (pinfunction "A_A") (pintype "passive"))
      (node (ref "TEENSY_3.6") (pin "20/A6") (pinfunction "20/A6/PWM_20/A6") (pintype "bidirectional"))
    )
    (net (code "25") (name "Net-(COL2-P)") (class "Default")
      (node (ref "COL2") (pin "1") (pinfunction "P_1") (pintype "passive"))
      (node (ref "D17") (pin "A") (pinfunction "A_A") (pintype "passive"))
      (node (ref "D18") (pin "A") (pinfunction "A_A") (pintype "passive"))
      (node (ref "D19") (pin "A") (pinfunction "A_A") (pintype "passive"))
      (node (ref "D20") (pin "A") (pinfunction "A_A") (pintype "passive"))
      (node (ref "SHIFT2") (pin "1") (pinfunction "1_1") (pintype "passive"))
      (node (ref "SHIFT2") (pin "2") (pinfunction "2_2") (pintype "passive"))
      (node (ref "TEENSY_3.6") (pin "33/A14") (pinfunction "33/A14/TX5/CAN1-TX_33/A14") (pintype "bidirectional"))
    )
    (net (code "26") (name "Net-(COL3-P)") (class "Default")
      (node (ref "COL3") (pin "1") (pinfunction "P_1") (pintype "passive"))
      (node (ref "D13") (pin "A") (pinfunction "A_A") (pintype "passive"))
      (node (ref "D14") (pin "A") (pinfunction "A_A") (pintype "passive"))
      (node (ref "D15") (pin "A") (pinfunction "A_A") (pintype "passive"))
      (node (ref "D16") (pin "A") (pinfunction "A_A") (pintype "passive"))
      (node (ref "SHIFT1") (pin "1") (pinfunction "1_1") (pintype "passive"))
      (node (ref "SHIFT1") (pin "2") (pinfunction "2_2") (pintype "passive"))
      (node (ref "TEENSY_3.6") (pin "34/A15") (pinfunction "34/A15/RX5/CAN1-RX_34/A15") (pintype "bidirectional"))
    )
    (net (code "27") (name "Net-(COL4-P)") (class "Default")
      (node (ref "COL4") (pin "1") (pinfunction "P_1") (pintype "passive"))
      (node (ref "D10") (pin "A") (pinfunction "A_A") (pintype "passive"))
      (node (ref "D11") (pin "A") (pinfunction "A_A") (pintype "passive"))
      (node (ref "D12") (pin "A") (pinfunction "A_A") (pintype "passive"))
      (node (ref "D9") (pin "A") (pinfunction "A_A") (pintype "passive"))
      (node (ref "TEENSY_3.6") (pin "25") (pinfunction "25_25") (pintype "bidirectional"))
    )
    (net (code "28") (name "Net-(COL5-P)") (class "Default")
      (node (ref "COL5") (pin "1") (pinfunction "P_1") (pintype "passive"))
      (node (ref "D5") (pin "A") (pinfunction "A_A") (pintype "passive"))
      (node (ref "D6") (pin "A") (pinfunction "A_A") (pintype "passive"))
      (node (ref "D7") (pin "A") (pinfunction "A_A") (pintype "passive"))
      (node (ref "D8") (pin "A") (pinfunction "A_A") (pintype "passive"))
      (node (ref "TEENSY_3.6") (pin "26") (pinfunction "26_26") (pintype "bidirectional"))
    )
    (net (code "29") (name "Net-(COL6-P)") (class "Default")
      (node (ref "COL6") (pin "1") (pinfunction "P_1") (pintype "passive"))
      (node (ref "D1") (pin "A") (pinfunction "A_A") (pintype "passive"))
      (node (ref "D2") (pin "A") (pinfunction "A_A") (pintype "passive"))
      (node (ref "D3") (pin "A") (pinfunction "A_A") (pintype "passive"))
      (node (ref "D4") (pin "A") (pinfunction "A_A") (pintype "passive"))
      (node (ref "TEENSY_3.6") (pin "21/A7") (pinfunction "21/A7/PWM_21/A7") (pintype "bidirectional"))
    )
    (net (code "30") (name "Net-(CS-P)") (class "Default")
      (node (ref "CS") (pin "1") (pinfunction "P_1") (pintype "passive"))
      (node (ref "TEENSY_3.6") (pin "6") (pinfunction "6/PWM_6") (pintype "bidirectional"))
      (node (ref "U$2") (pin "CS") (pinfunction "CS_CS") (pintype "input"))
      (node (ref "U$3") (pin "CS") (pinfunction "CS_CS") (pintype "input"))
      (node (ref "U$5") (pin "CS") (pinfunction "CS_CS") (pintype "input"))
    )
    (net (code "31") (name "Net-(D+-P)") (class "Default")
      (node (ref "D+") (pin "1") (pinfunction "P_1") (pintype "passive"))
      (node (ref "USB-B") (pin "D+") (pinfunction "D+_D+") (pintype "bidirectional"))
    )
    (net (code "32") (name "Net-(D--P)") (class "Default")
      (node (ref "D-") (pin "1") (pinfunction "P_1") (pintype "passive"))
      (node (ref "USB-B") (pin "D-") (pinfunction "D-_D-") (pintype "bidirectional"))
    )
    (net (code "33") (name "Net-(D1+-P)") (class "Default")
      (node (ref "D1+") (pin "1") (pinfunction "P_1") (pintype "passive"))
      (node (ref "TEENSY_3.6") (pin "D+") (pinfunction "D+_D+") (pintype "bidirectional"))
    )
    (net (code "34") (name "Net-(D1--P)") (class "Default")
      (node (ref "D1-") (pin "1") (pinfunction "P_1") (pintype "passive"))
      (node (ref "TEENSY_3.6") (pin "D-") (pinfunction "D-_D-") (pintype "bidirectional"))
    )
    (net (code "35") (name "Net-(D25-PadA)") (class "Default")
      (node (ref "D25") (pin "A") (pinfunction "A_A") (pintype "passive"))
      (node (ref "SHIFT1") (pin "3") (pinfunction "3_3") (pintype "passive"))
      (node (ref "SHIFT1") (pin "4") (pinfunction "4_4") (pintype "passive"))
    )
    (net (code "36") (name "Net-(D26-PadA)") (class "Default")
      (node (ref "D26") (pin "A") (pinfunction "A_A") (pintype "passive"))
      (node (ref "SHIFT2") (pin "3") (pinfunction "3_3") (pintype "passive"))
      (node (ref "SHIFT2") (pin "4") (pinfunction "4_4") (pintype "passive"))
    )
    (net (code "37") (name "Net-(DAC0-P)") (class "Default")
      (node (ref "DAC0") (pin "1") (pinfunction "P_1") (pintype "passive"))
      (node (ref "TEENSY_3.6") (pin "A21") (pinfunction "A21/DAC0_A21") (pintype "bidirectional"))
    )
    (net (code "38") (name "Net-(DAC1-P)") (class "Default")
      (node (ref "DAC1") (pin "1") (pinfunction "P_1") (pintype "passive"))
      (node (ref "TEENSY_3.6") (pin "A22") (pinfunction "A22/DAC1_A22") (pintype "bidirectional"))
    )
    (net (code "39") (name "Net-(DC-P)") (class "Default")
      (node (ref "DC") (pin "1") (pinfunction "P_1") (pintype "passive"))
      (node (ref "TEENSY_3.6") (pin "4") (pinfunction "4/CAN0-RX/SDA2/PWM_4") (pintype "bidirectional"))
      (node (ref "U$1") (pin "DC") (pinfunction "DC_DC") (pintype "bidirectional"))
      (node (ref "U$2") (pin "DC") (pinfunction "DC_DC") (pintype "bidirectional"))
      (node (ref "U$3") (pin "DC") (pinfunction "DC_DC") (pintype "bidirectional"))
      (node (ref "U$5") (pin "DC") (pinfunction "DC_DC") (pintype "bidirectional"))
    )
    (net (code "40") (name "Net-(DMX-OUT-1)") (class "Default")
      (node (ref "DMX-OUT") (pin "2") (pinfunction "1_2") (pintype "passive"))
      (node (ref "DMX2") (pin "1") (pinfunction "P_1") (pintype "passive"))
      (node (ref "SP485CNL") (pin "7") (pinfunction "B_7") (pintype "passive"))
    )
    (net (code "41") (name "Net-(DMX-OUT-2)") (class "Default")
      (node (ref "100R8") (pin "1") (pinfunction "1_1") (pintype "passive"))
      (node (ref "DMX-OUT") (pin "1") (pinfunction "2_1") (pintype "passive"))
      (node (ref "DMX-OUT") (pin "G") (pinfunction "G_G") (pintype "passive"))
    )
    (net (code "42") (name "Net-(DOUT-P)") (class "Default")
      (node (ref "DOUT") (pin "1") (pinfunction "P_1") (pintype "passive"))
      (node (ref "NEOPIXEL-DATAOUT") (pin "1") (pinfunction "P_1") (pintype "passive"))
      (node (ref "U$7") (pin "DOUT") (pinfunction "DOUT_DOUT") (pintype "bidirectional"))
    )
    (net (code "43") (name "Net-(ENC1-+)") (class "Default")
      (node (ref "ENC1") (pin "5") (pinfunction "+_5") (pintype "passive"))
      (node (ref "ENC2") (pin "5") (pinfunction "+_5") (pintype "passive"))
      (node (ref "TEENSY_3.6") (pin "3.3V") (pinfunction "3.3V_3.3V") (pintype "power_in"))
      (node (ref "U$1") (pin "VCC") (pinfunction "VCC_VCC") (pintype "power_in"))
      (node (ref "U$5") (pin "VCC") (pinfunction "VCC_VCC") (pintype "power_in"))
    )
    (net (code "44") (name "Net-(ENC1--B)") (class "Default")
      (node (ref "100R3") (pin "1") (pinfunction "1_1") (pintype "passive"))
      (node (ref "ENC1") (pin "4") (pinfunction "-B_4") (pintype "passive"))
    )
    (net (code "45") (name "Net-(ENC1--G)") (class "Default")
      (node (ref "100R2") (pin "1") (pinfunction "1_1") (pintype "passive"))
      (node (ref "ENC1") (pin "2") (pinfunction "-G_2") (pintype "passive"))
    )
    (net (code "46") (name "Net-(ENC1--R)") (class "Default")
      (node (ref "100R1") (pin "1") (pinfunction "1_1") (pintype "passive"))
      (node (ref "ENC1") (pin "1") (pinfunction "-R_1") (pintype "passive"))
    )
    (net (code "47") (name "Net-(ENC1-SW)") (class "Default")
      (node (ref "10KR1") (pin "2") (pinfunction "2_2") (pintype "passive"))
      (node (ref "220R1") (pin "1") (pinfunction "1_1") (pintype "passive"))
      (node (ref "ENC1") (pin "3") (pinfunction "SW_3") (pintype "passive"))
    )
    (net (code "48") (name "Net-(ENC2--B)") (class "Default")
      (node (ref "100R4") (pin "1") (pinfunction "1_1") (pintype "passive"))
      (node (ref "ENC2") (pin "4") (pinfunction "-B_4") (pintype "passive"))
    )
    (net (code "49") (name "Net-(ENC2--G)") (class "Default")
      (node (ref "100R6") (pin "1") (pinfunction "1_1") (pintype "passive"))
      (node (ref "ENC2") (pin "2") (pinfunction "-G_2") (pintype "passive"))
    )
    (net (code "50") (name "Net-(ENC2--R)") (class "Default")
      (node (ref "100R5") (pin "1") (pinfunction "1_1") (pintype "passive"))
      (node (ref "ENC2") (pin "1") (pinfunction "-R_1") (pintype "passive"))
    )
    (net (code "51") (name "Net-(ENC2-SW)") (class "Default")
      (node (ref "10KR2") (pin "2") (pinfunction "2_2") (pintype "passive"))
      (node (ref "220R4") (pin "1") (pinfunction "1_1") (pintype "passive"))
      (node (ref "ENC2") (pin "3") (pinfunction "SW_3") (pintype "passive"))
    )
    (net (code "52") (name "Net-(FSR-P)") (class "Default")
      (node (ref "100R7") (pin "2") (pinfunction "2_2") (pintype "passive"))
      (node (ref "FSR") (pin "1") (pinfunction "P_1") (pintype "passive"))
      (node (ref "OPA348,") (pin "4") (pinfunction "-IN_4") (pintype "input"))
    )
    (net (code "53") (name "Net-(MIDIIN4-P)") (class "Default")
      (node (ref "220R11") (pin "1") (pinfunction "1_1") (pintype "passive"))
      (node (ref "MIDIIN4") (pin "1") (pinfunction "P_1") (pintype "passive"))
    )
    (net (code "54") (name "Net-(MIDIOUT-P)") (class "Default")
      (node (ref "MIDIOUT") (pin "1") (pinfunction "P_1") (pintype "passive"))
      (node (ref "MIDIOUT.") (pin "1") (pinfunction "P_1") (pintype "passive"))
      (node (ref "TEENSY_3.6") (pin "10") (pinfunction "10/TX2/PWM_10") (pintype "bidirectional"))
    )
    (net (code "55") (name "Net-(MOSI-P)") (class "Default")
      (node (ref "MOSI") (pin "1") (pinfunction "P_1") (pintype "passive"))
      (node (ref "TEENSY_3.6") (pin "11") (pinfunction "11/MOSI0_11") (pintype "bidirectional"))
      (node (ref "U$1") (pin "SDA") (pinfunction "SDA_SDA") (pintype "input"))
      (node (ref "U$2") (pin "DIN") (pinfunction "DIN_DIN") (pintype "input"))
      (node (ref "U$3") (pin "DIN") (pinfunction "DIN_DIN") (pintype "input"))
      (node (ref "U$5") (pin "SDA") (pinfunction "SDA_SDA") (pintype "input"))
    )
    (net (code "56") (name "Net-(OPA348,A-OUT)") (class "Default")
      (node (ref "100R7") (pin "1") (pinfunction "1_1") (pintype "passive"))
      (node (ref "OPA348,") (pin "1") (pinfunction "OUT_1") (pintype "output"))
      (node (ref "TEENSY_3.6") (pin "22/A8") (pinfunction "22/A8/T/PWM_22/A8") (pintype "bidirectional"))
    )
    (net (code "57") (name "Net-(OPA348.A-+IN)") (class "Default")
      (node (ref "10KR3") (pin "1") (pinfunction "1_1") (pintype "passive"))
      (node (ref "10KR5") (pin "1") (pinfunction "1_1") (pintype "passive"))
      (node (ref "4.7µFC2") (pin "2") (pinfunction "2_2") (pintype "passive"))
      (node (ref "OPA348.") (pin "3") (pinfunction "+IN_3") (pintype "input"))
    )
    (net (code "58") (name "Net-(OPA348.A--IN)") (class "Default")
      (node (ref "10KR4") (pin "1") (pinfunction "1_1") (pintype "passive"))
      (node (ref "820KR1") (pin "2") (pinfunction "2_2") (pintype "passive"))
      (node (ref "OPA348.") (pin "4") (pinfunction "-IN_4") (pintype "input"))
    )
    (net (code "59") (name "Net-(PGM-1-Pad2)") (class "Default")
      (node (ref "PGM") (pin "1") (pinfunction "1_1") (pintype "passive"))
      (node (ref "PGM") (pin "2") (pinfunction "1_2") (pintype "passive"))
      (node (ref "TEENSY_3.6") (pin "PGM") (pinfunction "PGM_PGM") (pintype "bidirectional"))
    )
    (net (code "60") (name "Net-(ROW1-P)") (class "Default")
      (node (ref "ROW1") (pin "1") (pinfunction "P_1") (pintype "passive"))
      (node (ref "S1") (pin "1") (pinfunction "S_1") (pintype "passive"))
      (node (ref "SL1") (pin "4") (pinfunction "P1_4") (pintype "passive"))
      (node (ref "TEENSY_3.6") (pin "14/A0") (pinfunction "14/A0/PWM_14/A0") (pintype "bidirectional"))
    )
    (net (code "61") (name "Net-(ROW2-P)") (class "Default")
      (node (ref "ROW2") (pin "1") (pinfunction "P_1") (pintype "passive"))
      (node (ref "S6") (pin "1") (pinfunction "S_1") (pintype "passive"))
      (node (ref "S7") (pin "2") (pinfunction "S1_2") (pintype "passive"))
      (node (ref "TEENSY_3.6") (pin "15/A1") (pinfunction "15/A1/T_15/A1") (pintype "bidirectional"))
    )
    (net (code "62") (name "Net-(ROW3-P)") (class "Default")
      (node (ref "ROW3") (pin "1") (pinfunction "P_1") (pintype "passive"))
      (node (ref "S10") (pin "2") (pinfunction "S1_2") (pintype "passive"))
      (node (ref "S11") (pin "1") (pinfunction "S_1") (pintype "passive"))
      (node (ref "TEENSY_3.6") (pin "16/A2") (pinfunction "16/A2/T/PWM_16/A2") (pintype "bidirectional"))
    )
    (net (code "63") (name "Net-(ROW4-P)") (class "Default")
      (node (ref "ROW4") (pin "1") (pinfunction "P_1") (pintype "passive"))
      (node (ref "S13") (pin "2") (pinfunction "S1_2") (pintype "passive"))
      (node (ref "SL4") (pin "3") (pinfunction "P_3") (pintype "passive"))
      (node (ref "TEENSY_3.6") (pin "17/A3") (pinfunction "17/A3/T/PWM_17/A3") (pintype "bidirectional"))
    )
    (net (code "64") (name "Net-(ROW5-P)") (class "Default")
      (node (ref "D25") (pin "C") (pinfunction "C_C") (pintype "passive"))
      (node (ref "D26") (pin "C") (pinfunction "C_C") (pintype "passive"))
      (node (ref "ROW5") (pin "1") (pinfunction "P_1") (pintype "passive"))
      (node (ref "TEENSY_3.6") (pin "12") (pinfunction "12/MISO0_12") (pintype "bidirectional"))
    )
    (net (code "65") (name "Net-(RST-P)") (class "Default")
      (node (ref "RST") (pin "1") (pinfunction "P_1") (pintype "passive"))
      (node (ref "TEENSY_3.6") (pin "5") (pinfunction "5/PWM_5") (pintype "bidirectional"))
      (node (ref "U$1") (pin "RES") (pinfunction "RES_RES") (pintype "input"))
      (node (ref "U$2") (pin "RST") (pinfunction "RST_RST") (pintype "input"))
      (node (ref "U$3") (pin "RST") (pinfunction "RST_RST") (pintype "input"))
      (node (ref "U$5") (pin "RES") (pinfunction "RES_RES") (pintype "input"))
    )
    (net (code "66") (name "Net-(RX3-P)") (class "Default")
      (node (ref "220R10") (pin "1") (pinfunction "1_1") (pintype "passive"))
      (node (ref "RX3") (pin "1") (pinfunction "P_1") (pintype "passive"))
      (node (ref "TEENSY_3.6") (pin "7") (pinfunction "7/RX3/PWM_7") (pintype "bidirectional"))
    )
    (net (code "67") (name "Net-(RX3.-P)") (class "Default")
      (node (ref "220R10") (pin "2") (pinfunction "2_2") (pintype "passive"))
      (node (ref "RX3.") (pin "1") (pinfunction "P_1") (pintype "passive"))
    )
    (net (code "68") (name "Net-(S1-P1)") (class "Default")
      (node (ref "D17") (pin "C") (pinfunction "C_C") (pintype "passive"))
      (node (ref "S1") (pin "4") (pinfunction "P1_4") (pintype "passive"))
    )
    (net (code "69") (name "Net-(S1-S1)") (class "Default")
      (node (ref "S1") (pin "2") (pinfunction "S1_2") (pintype "passive"))
      (node (ref "S2") (pin "1") (pinfunction "S_1") (pintype "passive"))
    )
    (net (code "70") (name "Net-(S2-P1)") (class "Default")
      (node (ref "D13") (pin "C") (pinfunction "C_C") (pintype "passive"))
      (node (ref "S2") (pin "4") (pinfunction "P1_4") (pintype "passive"))
    )
    (net (code "71") (name "Net-(S2-S1)") (class "Default")
      (node (ref "S2") (pin "2") (pinfunction "S1_2") (pintype "passive"))
      (node (ref "S3") (pin "1") (pinfunction "S_1") (pintype "passive"))
    )
    (net (code "72") (name "Net-(S3-P1)") (class "Default")
      (node (ref "D9") (pin "C") (pinfunction "C_C") (pintype "passive"))
      (node (ref "S3") (pin "4") (pinfunction "P1_4") (pintype "passive"))
    )
    (net (code "73") (name "Net-(S3-S1)") (class "Default")
      (node (ref "S3") (pin "2") (pinfunction "S1_2") (pintype "passive"))
      (node (ref "S4") (pin "1") (pinfunction "S_1") (pintype "passive"))
    )
    (net (code "74") (name "Net-(S4-P1)") (class "Default")
      (node (ref "D5") (pin "C") (pinfunction "C_C") (pintype "passive"))
      (node (ref "S4") (pin "4") (pinfunction "P1_4") (pintype "passive"))
    )
    (net (code "75") (name "Net-(S4-S1)") (class "Default")
      (node (ref "S4") (pin "2") (pinfunction "S1_2") (pintype "passive"))
      (node (ref "SR1") (pin "3") (pinfunction "P_3") (pintype "passive"))
    )
    (net (code "76") (name "Net-(S5-P1)") (class "Default")
      (node (ref "D18") (pin "C") (pinfunction "C_C") (pintype "passive"))
      (node (ref "S5") (pin "4") (pinfunction "P1_4") (pintype "passive"))
    )
    (net (code "77") (name "Net-(S5-S)") (class "Default")
      (node (ref "S5") (pin "1") (pinfunction "S_1") (pintype "passive"))
      (node (ref "S6") (pin "2") (pinfunction "S1_2") (pintype "passive"))
    )
    (net (code "78") (name "Net-(S5-S1)") (class "Default")
      (node (ref "S5") (pin "2") (pinfunction "S1_2") (pintype "passive"))
      (node (ref "SL2") (pin "3") (pinfunction "P_3") (pintype "passive"))
    )
    (net (code "79") (name "Net-(S6-P1)") (class "Default")
      (node (ref "D14") (pin "C") (pinfunction "C_C") (pintype "passive"))
      (node (ref "S6") (pin "4") (pinfunction "P1_4") (pintype "passive"))
    )
    (net (code "80") (name "Net-(S7-P1)") (class "Default")
      (node (ref "D10") (pin "C") (pinfunction "C_C") (pintype "passive"))
      (node (ref "S7") (pin "4") (pinfunction "P1_4") (pintype "passive"))
    )
    (net (code "81") (name "Net-(S7-S)") (class "Default")
      (node (ref "S7") (pin "1") (pinfunction "S_1") (pintype "passive"))
      (node (ref "S8") (pin "2") (pinfunction "S1_2") (pintype "passive"))
    )
    (net (code "82") (name "Net-(S8-P1)") (class "Default")
      (node (ref "D6") (pin "C") (pinfunction "C_C") (pintype "passive"))
      (node (ref "S8") (pin "4") (pinfunction "P1_4") (pintype "passive"))
    )
    (net (code "83") (name "Net-(S8-S)") (class "Default")
      (node (ref "S8") (pin "1") (pinfunction "S_1") (pintype "passive"))
      (node (ref "SR2") (pin "4") (pinfunction "P1_4") (pintype "passive"))
    )
    (net (code "84") (name "Net-(S9-P1)") (class "Default")
      (node (ref "D19") (pin "C") (pinfunction "C_C") (pintype "passive"))
      (node (ref "S9") (pin "4") (pinfunction "P1_4") (pintype "passive"))
    )
    (net (code "85") (name "Net-(S9-S)") (class "Default")
      (node (ref "S9") (pin "1") (pinfunction "S_1") (pintype "passive"))
      (node (ref "SL3") (pin "4") (pinfunction "P1_4") (pintype "passive"))
    )
    (net (code "86") (name "Net-(S10-P1)") (class "Default")
      (node (ref "D15") (pin "C") (pinfunction "C_C") (pintype "passive"))
      (node (ref "S10") (pin "4") (pinfunction "P1_4") (pintype "passive"))
    )
    (net (code "87") (name "Net-(S10-S)") (class "Default")
      (node (ref "S10") (pin "1") (pinfunction "S_1") (pintype "passive"))
      (node (ref "S9") (pin "2") (pinfunction "S1_2") (pintype "passive"))
    )
    (net (code "88") (name "Net-(S11-P1)") (class "Default")
      (node (ref "D11") (pin "C") (pinfunction "C_C") (pintype "passive"))
      (node (ref "S11") (pin "4") (pinfunction "P1_4") (pintype "passive"))
    )
    (net (code "89") (name "Net-(S11-S1)") (class "Default")
      (node (ref "S11") (pin "2") (pinfunction "S1_2") (pintype "passive"))
      (node (ref "S12") (pin "1") (pinfunction "S_1") (pintype "passive"))
    )
    (net (code "90") (name "Net-(S12-P1)") (class "Default")
      (node (ref "D7") (pin "C") (pinfunction "C_C") (pintype "passive"))
      (node (ref "S12") (pin "4") (pinfunction "P1_4") (pintype "passive"))
    )
    (net (code "91") (name "Net-(S12-S1)") (class "Default")
      (node (ref "S12") (pin "2") (pinfunction "S1_2") (pintype "passive"))
      (node (ref "SR3") (pin "3") (pinfunction "P_3") (pintype "passive"))
    )
    (net (code "92") (name "Net-(S13-P1)") (class "Default")
      (node (ref "D20") (pin "C") (pinfunction "C_C") (pintype "passive"))
      (node (ref "S13") (pin "4") (pinfunction "P1_4") (pintype "passive"))
    )
    (net (code "93") (name "Net-(S13-S)") (class "Default")
      (node (ref "S13") (pin "1") (pinfunction "S_1") (pintype "passive"))
      (node (ref "S14") (pin "2") (pinfunction "S1_2") (pintype "passive"))
    )
    (net (code "94") (name "Net-(S14-P1)") (class "Default")
      (node (ref "D16") (pin "C") (pinfunction "C_C") (pintype "passive"))
      (node (ref "S14") (pin "4") (pinfunction "P1_4") (pintype "passive"))
    )
    (net (code "95") (name "Net-(S14-S)") (class "Default")
      (node (ref "S14") (pin "1") (pinfunction "S_1") (pintype "passive"))
      (node (ref "S15") (pin "2") (pinfunction "S1_2") (pintype "passive"))
    )
    (net (code "96") (name "Net-(S15-P1)") (class "Default")
      (node (ref "D12") (pin "C") (pinfunction "C_C") (pintype "passive"))
      (node (ref "S15") (pin "4") (pinfunction "P1_4") (pintype "passive"))
    )
    (net (code "97") (name "Net-(S15-S)") (class "Default")
      (node (ref "S15") (pin "1") (pinfunction "S_1") (pintype "passive"))
      (node (ref "S16") (pin "2") (pinfunction "S1_2") (pintype "passive"))
    )
    (net (code "98") (name "Net-(S16-P1)") (class "Default")
      (node (ref "D8") (pin "C") (pinfunction "C_C") (pintype "passive"))
      (node (ref "S16") (pin "4") (pinfunction "P1_4") (pintype "passive"))
    )
    (net (code "99") (name "Net-(S16-S)") (class "Default")
      (node (ref "S16") (pin "1") (pinfunction "S_1") (pintype "passive"))
      (node (ref "SR4") (pin "4") (pinfunction "P1_4") (pintype "passive"))
    )
    (net (code "100") (name "Net-(SCK-P)") (class "Default")
      (node (ref "SCK") (pin "1") (pinfunction "P_1") (pintype "passive"))
      (node (ref "TEENSY_3.6") (pin "13") (pinfunction "13/SCK0/LED_13") (pintype "bidirectional"))
      (node (ref "U$1") (pin "SCL") (pinfunction "SCL_SCL") (pintype "input"))
      (node (ref "U$2") (pin "CLK") (pinfunction "CLK_CLK") (pintype "input"))
      (node (ref "U$3") (pin "SCK") (pinfunction "SCK_SCK") (pintype "input"))
      (node (ref "U$5") (pin "SCL") (pinfunction "SCL_SCL") (pintype "input"))
    )
    (net (code "101") (name "Net-(SCL-P)") (class "Default")
      (node (ref "220R8") (pin "2") (pinfunction "2_2") (pintype "passive"))
      (node (ref "SCL") (pin "1") (pinfunction "P_1") (pintype "passive"))
      (node (ref "TEENSY_3.6") (pin "19/A5") (pinfunction "19/A5/T/SCL0_19/A5") (pintype "bidirectional"))
    )
    (net (code "102") (name "Net-(SCL.-P)") (class "Default")
      (node (ref "220R8") (pin "1") (pinfunction "1_1") (pintype "passive"))
      (node (ref "SCL.") (pin "1") (pinfunction "P_1") (pintype "passive"))
    )
    (net (code "103") (name "Net-(SDA-P)") (class "Default")
      (node (ref "220R7") (pin "2") (pinfunction "2_2") (pintype "passive"))
      (node (ref "SDA") (pin "1") (pinfunction "P_1") (pintype "passive"))
      (node (ref "TEENSY_3.6") (pin "18/A4") (pinfunction "18/A4/T/SDA0_18/A4") (pintype "bidirectional"))
    )
    (net (code "104") (name "Net-(SDA.-P)") (class "Default")
      (node (ref "220R7") (pin "1") (pinfunction "1_1") (pintype "passive"))
      (node (ref "SDA.") (pin "1") (pinfunction "P_1") (pintype "passive"))
    )
    (net (code "105") (name "Net-(SL1-S1)") (class "Default")
      (node (ref "D21") (pin "C") (pinfunction "C_C") (pintype "passive"))
      (node (ref "SL1") (pin "2") (pinfunction "S1_2") (pintype "passive"))
    )
    (net (code "106") (name "Net-(SL2-S1)") (class "Default")
      (node (ref "D22") (pin "C") (pinfunction "C_C") (pintype "passive"))
      (node (ref "SL2") (pin "2") (pinfunction "S1_2") (pintype "passive"))
    )
    (net (code "107") (name "Net-(SL3-S1)") (class "Default")
      (node (ref "D23") (pin "C") (pinfunction "C_C") (pintype "passive"))
      (node (ref "SL3") (pin "2") (pinfunction "S1_2") (pintype "passive"))
    )
    (net (code "108") (name "Net-(SL4-S1)") (class "Default")
      (node (ref "D24") (pin "C") (pinfunction "C_C") (pintype "passive"))
      (node (ref "SL4") (pin "2") (pinfunction "S1_2") (pintype "passive"))
    )
    (net (code "109") (name "Net-(SP485CNL-DE)") (class "Default")
      (node (ref "SP485CNL") (pin "2") (pinfunction "RE/_2") (pintype "input"))
      (node (ref "SP485CNL") (pin "3") (pinfunction "DE_3") (pintype "input"))
      (node (ref "TEENSY_3.6") (pin "2") (pinfunction "2/PWM_2") (pintype "bidirectional"))
    )
    (net (code "110") (name "Net-(SP485CNL-DI)") (class "Default")
      (node (ref "SP485CNL") (pin "4") (pinfunction "DI_4") (pintype "input"))
      (node (ref "TEENSY_3.6") (pin "1") (pinfunction "1/TX1/MISO1/T_1") (pintype "bidirectional"))
    )
    (net (code "111") (name "Net-(SP485CNL-RO)") (class "Default")
      (node (ref "SP485CNL") (pin "1") (pinfunction "RO_1") (pintype "output"))
      (node (ref "TEENSY_3.6") (pin "0") (pinfunction "0/RX1/MOSI1/T_0") (pintype "bidirectional"))
    )
    (net (code "112") (name "Net-(SR1-S)") (class "Default")
      (node (ref "D1") (pin "C") (pinfunction "C_C") (pintype "passive"))
      (node (ref "SR1") (pin "1") (pinfunction "S_1") (pintype "passive"))
    )
    (net (code "113") (name "Net-(SR2-S)") (class "Default")
      (node (ref "D2") (pin "C") (pinfunction "C_C") (pintype "passive"))
      (node (ref "SR2") (pin "1") (pinfunction "S_1") (pintype "passive"))
    )
    (net (code "114") (name "Net-(SR3-S)") (class "Default")
      (node (ref "D3") (pin "C") (pinfunction "C_C") (pintype "passive"))
      (node (ref "SR3") (pin "1") (pinfunction "S_1") (pintype "passive"))
    )
    (net (code "115") (name "Net-(SR4-S)") (class "Default")
      (node (ref "D4") (pin "C") (pinfunction "C_C") (pintype "passive"))
      (node (ref "SR4") (pin "1") (pinfunction "S_1") (pintype "passive"))
    )
    (net (code "116") (name "Net-(TEENSY_3.6-3{slash}CAN0-TX{slash}SCL2{slash}PWM)") (class "Default")
      (node (ref "TEENSY_3.6") (pin "3") (pinfunction "3/CAN0-TX/SCL2/PWM_3") (pintype "bidirectional"))
      (node (ref "U$1") (pin "BLK") (pinfunction "BLK_BLK") (pintype "input"))
      (node (ref "U$3") (pin "BL") (pinfunction "BL_BL") (pintype "input"))
      (node (ref "U$5") (pin "BL") (pinfunction "BL_BL") (pintype "input"))
    )
    (net (code "117") (name "Net-(TEENSY_3.6-8{slash}TX3{slash}PWM)") (class "Default")
      (node (ref "220R9") (pin "1") (pinfunction "1_1") (pintype "passive"))
      (node (ref "TEENSY_3.6") (pin "8") (pinfunction "8/TX3/PWM_8") (pintype "bidirectional"))
      (node (ref "TX3") (pin "1") (pinfunction "P_1") (pintype "passive"))
    )
    (net (code "118") (name "Net-(TEENSY_3.6-23{slash}A9{slash}T{slash}PWM)") (class "Default")
      (node (ref "TEENSY_3.6") (pin "23/A9") (pinfunction "23/A9/T/PWM_23/A9") (pintype "bidirectional"))
      (node (ref "U$4") (pin "DIN") (pinfunction "DIN_DIN") (pintype "input"))
    )
    (net (code "119") (name "Net-(TEENSY_3.6-29{slash}T{slash}PWM)") (class "Default")
      (node (ref "100R3") (pin "2") (pinfunction "2_2") (pintype "passive"))
      (node (ref "TEENSY_3.6") (pin "29") (pinfunction "29/T/PWM_29") (pintype "bidirectional"))
    )
    (net (code "120") (name "Net-(TEENSY_3.6-30{slash}T{slash}PWM)") (class "Default")
      (node (ref "100R4") (pin "2") (pinfunction "2_2") (pintype "passive"))
      (node (ref "TEENSY_3.6") (pin "30") (pinfunction "30/T/PWM_30") (pintype "bidirectional"))
    )
    (net (code "121") (name "Net-(TEENSY_3.6-31{slash}A12{slash}RX4)") (class "Default")
      (node (ref "220R5") (pin "2") (pinfunction "2_2") (pintype "passive"))
      (node (ref "47NC3") (pin "1") (pinfunction "1_1") (pintype "passive"))
      (node (ref "TEENSY_3.6") (pin "31/A12") (pinfunction "31/A12/RX4_31/A12") (pintype "bidirectional"))
    )
    (net (code "122") (name "Net-(TEENSY_3.6-32{slash}A13{slash}TX4{slash}SCK1)") (class "Default")
      (node (ref "220R6") (pin "2") (pinfunction "2_2") (pintype "passive"))
      (node (ref "47NC4") (pin "1") (pinfunction "1_1") (pintype "passive"))
      (node (ref "TEENSY_3.6") (pin "32/A13") (pinfunction "32/A13/TX4/SCK1_32/A13") (pintype "bidirectional"))
    )
    (net (code "123") (name "Net-(TEENSY_3.6-35{slash}A16{slash}PWM)") (class "Default")
      (node (ref "100R1") (pin "2") (pinfunction "2_2") (pintype "passive"))
      (node (ref "TEENSY_3.6") (pin "35/A16") (pinfunction "35/A16/PWM_35/A16") (pintype "bidirectional"))
    )
    (net (code "124") (name "Net-(TEENSY_3.6-36{slash}A17{slash}PWM)") (class "Default")
      (node (ref "100R2") (pin "2") (pinfunction "2_2") (pintype "passive"))
      (node (ref "TEENSY_3.6") (pin "36/A17") (pinfunction "36/A17/PWM_36/A17") (pintype "bidirectional"))
    )
    (net (code "125") (name "Net-(TEENSY_3.6-37{slash}A18{slash}SCL1{slash}PWM)") (class "Default")
      (node (ref "100R6") (pin "2") (pinfunction "2_2") (pintype "passive"))
      (node (ref "TEENSY_3.6") (pin "37/A18") (pinfunction "37/A18/SCL1/PWM_37/A18") (pintype "bidirectional"))
    )
    (net (code "126") (name "Net-(TEENSY_3.6-38{slash}A19{slash}SDA1{slash}PWM)") (class "Default")
      (node (ref "100R5") (pin "2") (pinfunction "2_2") (pintype "passive"))
      (node (ref "TEENSY_3.6") (pin "38/A19") (pinfunction "38/A19/SDA1/PWM_38/A19") (pintype "bidirectional"))
    )
    (net (code "127") (name "Net-(TX3.-P)") (class "Default")
      (node (ref "220R9") (pin "2") (pinfunction "2_2") (pintype "passive"))
      (node (ref "TX3.") (pin "1") (pinfunction "P_1") (pintype "passive"))
    )
    (net (code "128") (name "Net-(V+-P)") (class "Default")
      (node (ref "TEENSY_3.6") (pin "VUSB1") (pinfunction "VUSB1_VUSB1") (pintype "power_in"))
      (node (ref "V+") (pin "1") (pinfunction "P_1") (pintype "passive"))
    )
    (net (code "129") (name "unconnected-(S1-P-Pad3)") (class "Default")
      (node (ref "S1") (pin "3") (pinfunction "P_3") (pintype "passive"))
    )
    (net (code "130") (name "unconnected-(S2-P-Pad3)") (class "Default")
      (node (ref "S2") (pin "3") (pinfunction "P_3") (pintype "passive"))
    )
    (net (code "131") (name "unconnected-(S3-P-Pad3)") (class "Default")
      (node (ref "S3") (pin "3") (pinfunction "P_3") (pintype "passive"))
    )
    (net (code "132") (name "unconnected-(S4-P-Pad3)") (class "Default")
      (node (ref "S4") (pin "3") (pinfunction "P_3") (pintype "passive"))
    )
    (net (code "133") (name "unconnected-(S5-P-Pad3)") (class "Default")
      (node (ref "S5") (pin "3") (pinfunction "P_3") (pintype "passive"))
    )
    (net (code "134") (name "unconnected-(S6-P-Pad3)") (class "Default")
      (node (ref "S6") (pin "3") (pinfunction "P_3") (pintype "passive"))
    )
    (net (code "135") (name "unconnected-(S7-P-Pad3)") (class "Default")
      (node (ref "S7") (pin "3") (pinfunction "P_3") (pintype "passive"))
    )
    (net (code "136") (name "unconnected-(S8-P-Pad3)") (class "Default")
      (node (ref "S8") (pin "3") (pinfunction "P_3") (pintype "passive"))
    )
    (net (code "137") (name "unconnected-(S9-P-Pad3)") (class "Default")
      (node (ref "S9") (pin "3") (pinfunction "P_3") (pintype "passive"))
    )
    (net (code "138") (name "unconnected-(S10-P-Pad3)") (class "Default")
      (node (ref "S10") (pin "3") (pinfunction "P_3") (pintype "passive"))
    )
    (net (code "139") (name "unconnected-(S11-P-Pad3)") (class "Default")
      (node (ref "S11") (pin "3") (pinfunction "P_3") (pintype "passive"))
    )
    (net (code "140") (name "unconnected-(S12-P-Pad3)") (class "Default")
      (node (ref "S12") (pin "3") (pinfunction "P_3") (pintype "passive"))
    )
    (net (code "141") (name "unconnected-(S13-P-Pad3)") (class "Default")
      (node (ref "S13") (pin "3") (pinfunction "P_3") (pintype "passive"))
    )
    (net (code "142") (name "unconnected-(S14-P-Pad3)") (class "Default")
      (node (ref "S14") (pin "3") (pinfunction "P_3") (pintype "passive"))
    )
    (net (code "143") (name "unconnected-(S15-P-Pad3)") (class "Default")
      (node (ref "S15") (pin "3") (pinfunction "P_3") (pintype "passive"))
    )
    (net (code "144") (name "unconnected-(S16-P-Pad3)") (class "Default")
      (node (ref "S16") (pin "3") (pinfunction "P_3") (pintype "passive"))
    )
    (net (code "145") (name "unconnected-(SL1-P-Pad3)") (class "Default")
      (node (ref "SL1") (pin "3") (pinfunction "P_3") (pintype "passive"))
    )
    (net (code "146") (name "unconnected-(SL1-S-Pad1)") (class "Default")
      (node (ref "SL1") (pin "1") (pinfunction "S_1") (pintype "passive"))
    )
    (net (code "147") (name "unconnected-(SL2-P1-Pad4)") (class "Default")
      (node (ref "SL2") (pin "4") (pinfunction "P1_4") (pintype "passive"))
    )
    (net (code "148") (name "unconnected-(SL2-S-Pad1)") (class "Default")
      (node (ref "SL2") (pin "1") (pinfunction "S_1") (pintype "passive"))
    )
    (net (code "149") (name "unconnected-(SL3-P-Pad3)") (class "Default")
      (node (ref "SL3") (pin "3") (pinfunction "P_3") (pintype "passive"))
    )
    (net (code "150") (name "unconnected-(SL3-S-Pad1)") (class "Default")
      (node (ref "SL3") (pin "1") (pinfunction "S_1") (pintype "passive"))
    )
    (net (code "151") (name "unconnected-(SL4-P1-Pad4)") (class "Default")
      (node (ref "SL4") (pin "4") (pinfunction "P1_4") (pintype "passive"))
    )
    (net (code "152") (name "unconnected-(SL4-S-Pad1)") (class "Default")
      (node (ref "SL4") (pin "1") (pinfunction "S_1") (pintype "passive"))
    )
    (net (code "153") (name "unconnected-(SR1-P1-Pad4)") (class "Default")
      (node (ref "SR1") (pin "4") (pinfunction "P1_4") (pintype "passive"))
    )
    (net (code "154") (name "unconnected-(SR1-S1-Pad2)") (class "Default")
      (node (ref "SR1") (pin "2") (pinfunction "S1_2") (pintype "passive"))
    )
    (net (code "155") (name "unconnected-(SR2-P-Pad3)") (class "Default")
      (node (ref "SR2") (pin "3") (pinfunction "P_3") (pintype "passive"))
    )
    (net (code "156") (name "unconnected-(SR2-S1-Pad2)") (class "Default")
      (node (ref "SR2") (pin "2") (pinfunction "S1_2") (pintype "passive"))
    )
    (net (code "157") (name "unconnected-(SR3-P1-Pad4)") (class "Default")
      (node (ref "SR3") (pin "4") (pinfunction "P1_4") (pintype "passive"))
    )
    (net (code "158") (name "unconnected-(SR3-S1-Pad2)") (class "Default")
      (node (ref "SR3") (pin "2") (pinfunction "S1_2") (pintype "passive"))
    )
    (net (code "159") (name "unconnected-(SR4-P-Pad3)") (class "Default")
      (node (ref "SR4") (pin "3") (pinfunction "P_3") (pintype "passive"))
    )
    (net (code "160") (name "unconnected-(SR4-S1-Pad2)") (class "Default")
      (node (ref "SR4") (pin "2") (pinfunction "S1_2") (pintype "passive"))
    )
    (net (code "161") (name "unconnected-(TEENSY_3.6-PadRESET)") (class "Default")
      (node (ref "TEENSY_3.6") (pin "RESET") (pinfunction "RESET_RESET") (pintype "bidirectional"))
    )
  )
)
